# preamp.net
KiCad netlist of a schematic drawn in Altium Designer
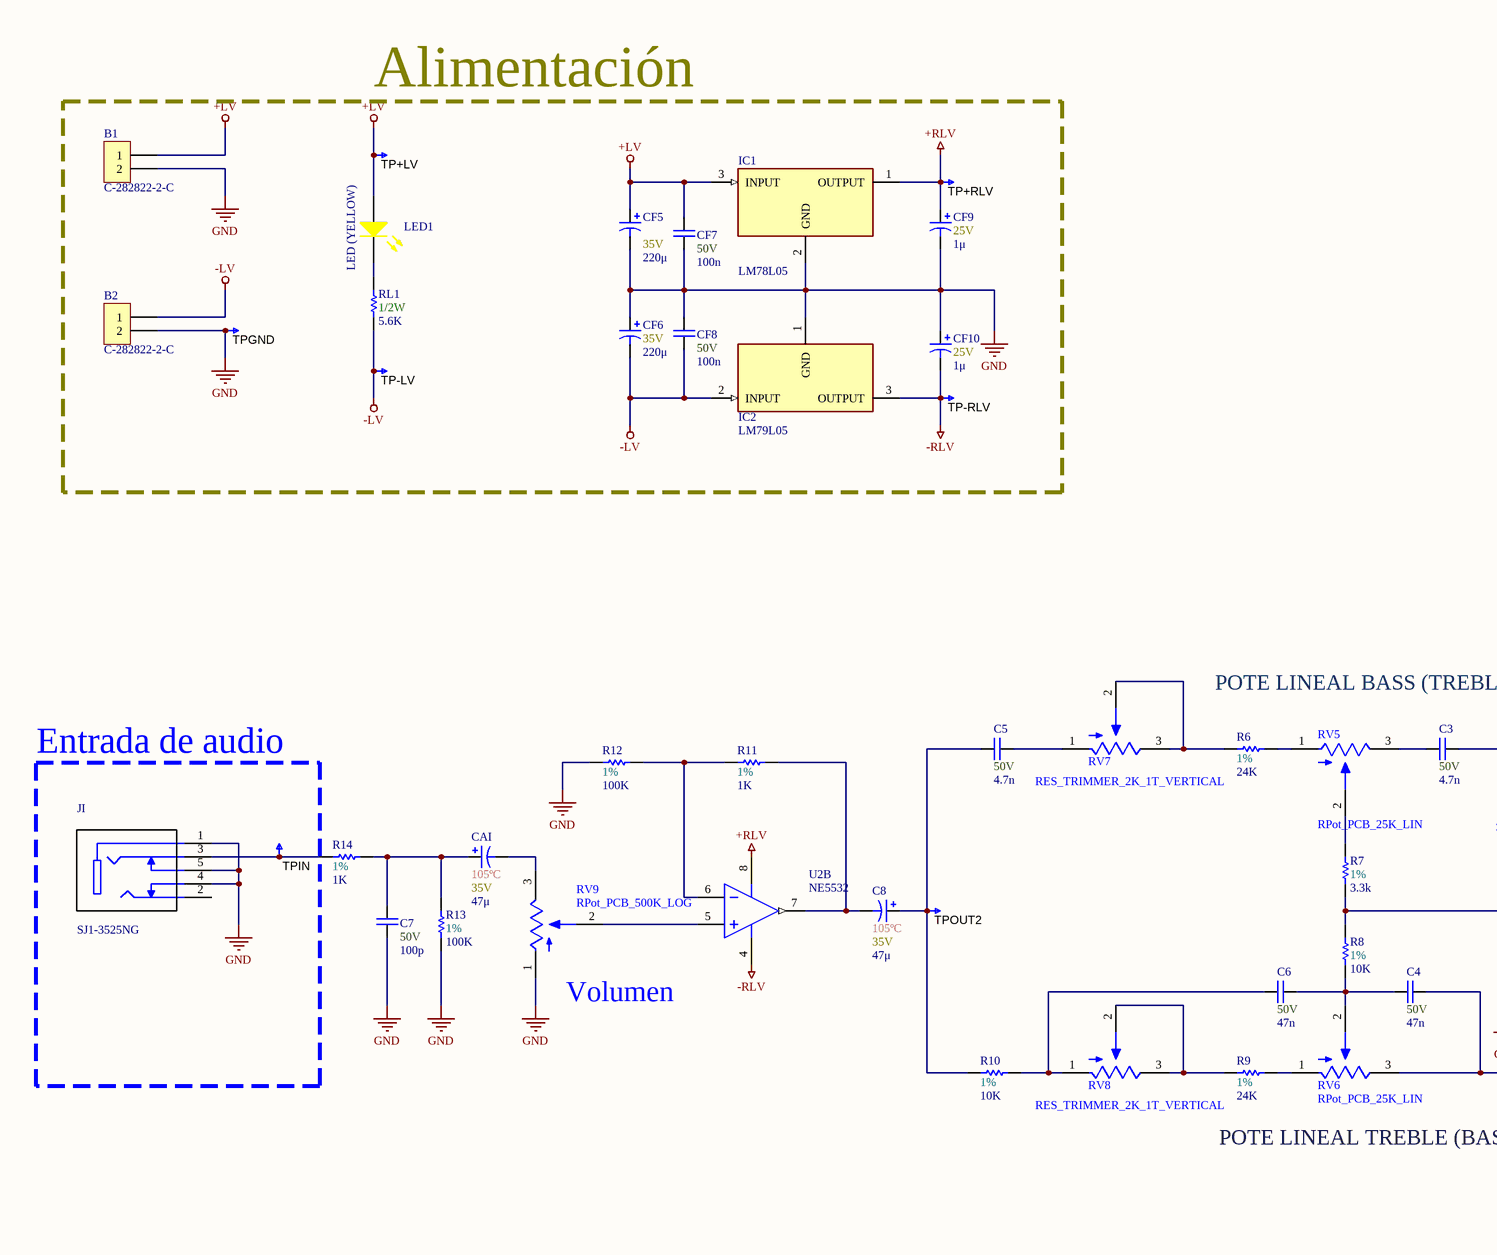
[diagram p0: preamp.SchDoc, left]
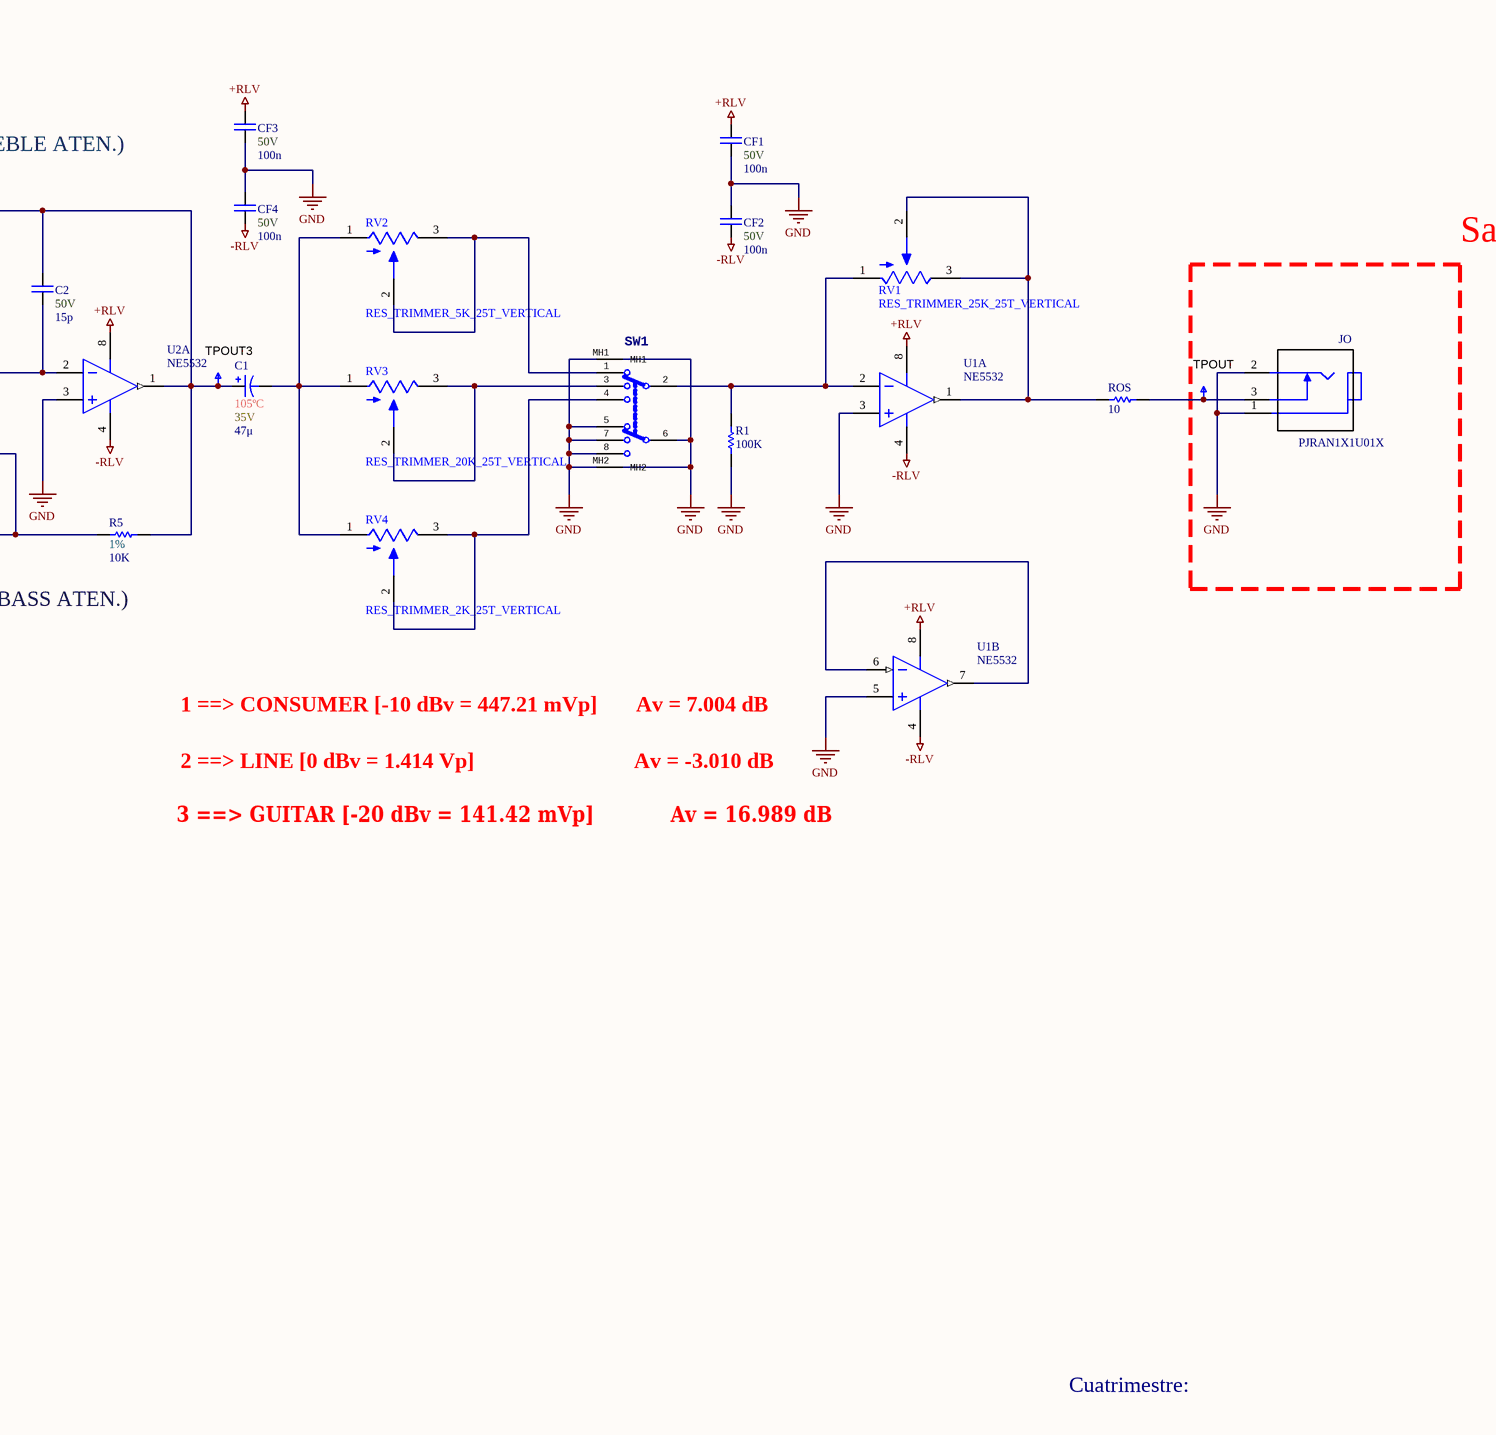
[diagram p1: preamp.SchDoc, right]

(export (version "E")
  (design (tool "Eeschema 10.0.6"))
  (components
    (comp (ref "B1")
      (value "C-282822-2-C")
      (footprint "TE-C-282822-2-C-PLUGGED")
      (description "TERMI-BLOK HEADER,ASSY90 2P - serie 282822 - 5.00mm")
      (fields (field (name "MANUFACTURER") "TE Connectivity"))
      (libsource (lib "Connectors") (part "C-282822-2-C"))
    )
    (comp (ref "B2")
      (value "C-282822-2-C")
      (footprint "TE-C-282822-2-C-PLUGGED")
      (description "TERMI-BLOK HEADER,ASSY90 2P - serie 282822 - 5.00mm")
      (fields (field (name "MANUFACTURER") "TE Connectivity"))
      (libsource (lib "Connectors") (part "C-282822-2-C"))
    )
    (comp (ref "C1")
      (value "47μ")
      (footprint "Al. Electrolytic 6.3mmx11.0mmx2.5mm-CLEAN")
      (description "Aluminum Electrolytic Capacitor 47μF 35V 20% 105º")
      (fields
        (field (name "TOLERANCE") "20%")
        (field (name "TEMPERATURE") "105ºC")
        (field (name "VOLTAGE") "35V")
        (field (name "Comment") "Al. Elect. 47u 35V 20% 105º")
      )
      (libsource (lib "Capacitors") (part "Al. Elect. 47u 35V 20% 105º"))
    )
    (comp (ref "C2")
      (value "15p")
      (footprint "Cer. pitch 5.08mm height 6.00mm")
      (description "Ceramic Capacitor 15pF 50V 10%")
      (fields
        (field (name "TOLERANCE") "10%")
        (field (name "VOLTAGE") "50V")
        (field (name "Comment") "Cer. 15p 50V 10%")
      )
      (libsource (lib "Capacitors") (part "Cer. 15p 50V 10%"))
    )
    (comp (ref "C3")
      (value "4.7n")
      (footprint "Cer. pitch 5.5mm height 6.0mm")
      (description "Ceramic Capacitor 4.7nF 50V 10%")
      (fields
        (field (name "TOLERANCE") "10%")
        (field (name "VOLTAGE") "50V")
        (field (name "Comment") "Cer. 4.7n 50V 10%")
      )
      (libsource (lib "Capacitors") (part "Cer. 4.7n 50V 10%"))
    )
    (comp (ref "C4")
      (value "47n")
      (footprint "Cer. pitch 5.5mm height 6.0mm")
      (description "Ceramic Capacitor 47nF 50V 10%")
      (fields
        (field (name "TOLERANCE") "10%")
        (field (name "VOLTAGE") "50V")
        (field (name "Comment") "Cer. 47n 50V 10%")
      )
      (libsource (lib "Capacitors") (part "Cer. 47n 50V 10%"))
    )
    (comp (ref "C5")
      (value "4.7n")
      (footprint "Cer. pitch 5.5mm height 6.0mm")
      (description "Ceramic Capacitor 4.7nF 50V 10%")
      (fields
        (field (name "TOLERANCE") "10%")
        (field (name "VOLTAGE") "50V")
        (field (name "Comment") "Cer. 4.7n 50V 10%")
      )
      (libsource (lib "Capacitors") (part "Cer. 4.7n 50V 10%"))
    )
    (comp (ref "C6")
      (value "47n")
      (footprint "Cer. pitch 5.5mm height 6.0mm")
      (description "Ceramic Capacitor 47nF 50V 10%")
      (fields
        (field (name "TOLERANCE") "10%")
        (field (name "VOLTAGE") "50V")
        (field (name "Comment") "Cer. 47n 50V 10%")
      )
      (libsource (lib "Capacitors") (part "Cer. 47n 50V 10%"))
    )
    (comp (ref "C7")
      (value "100p")
      (footprint "Cer. pitch 5.08mm height 6.00mm")
      (description "Ceramic Capacitor 100pF 50V 10%")
      (fields
        (field (name "TOLERANCE") "10%")
        (field (name "VOLTAGE") "50V")
        (field (name "Comment") "Cer. 100p 50V 10%")
      )
      (libsource (lib "Capacitors") (part "Cer. 100p 50V 10%"))
    )
    (comp (ref "C8")
      (value "47μ")
      (footprint "Al. Electrolytic 6.3mmx11.0mmx2.5mm-CLEAN")
      (description "Aluminum Electrolytic Capacitor 47μF 35V 20% 105º")
      (fields
        (field (name "TOLERANCE") "20%")
        (field (name "TEMPERATURE") "105ºC")
        (field (name "VOLTAGE") "35V")
        (field (name "Comment") "Al. Elect. 47u 35V 20% 105º")
      )
      (libsource (lib "") (part "Al. Elect. 47u 35V 20% 105º_1"))
    )
    (comp (ref "CAI")
      (value "47μ")
      (footprint "Al. Electrolytic 6.3mmx11.0mmx2.5mm-CLEAN")
      (description "Aluminum Electrolytic Capacitor 47μF 35V 20% 105º")
      (fields
        (field (name "TOLERANCE") "20%")
        (field (name "TEMPERATURE") "105ºC")
        (field (name "VOLTAGE") "35V")
        (field (name "Comment") "Al. Elect. 47u 35V 20% 105º")
      )
      (libsource (lib "Capacitors") (part "Al. Elect. 47u 35V 20% 105º"))
    )
    (comp (ref "CF1")
      (value "100n")
      (footprint "Cer. pitch 5.0mm height 5.5mm")
      (description "Ceramic Capacitor 100nF 50V 10%")
      (fields
        (field (name "TOLERANCE") "10%")
        (field (name "VOLTAGE") "50V")
        (field (name "Comment") "Cer. 100n 50V 10%")
      )
      (libsource (lib "Capacitors") (part "Cer. 100n 50V 10%"))
    )
    (comp (ref "CF2")
      (value "100n")
      (footprint "Cer. pitch 5.0mm height 5.5mm")
      (description "Ceramic Capacitor 100nF 50V 10%")
      (fields
        (field (name "TOLERANCE") "10%")
        (field (name "VOLTAGE") "50V")
        (field (name "Comment") "Cer. 100n 50V 10%")
      )
      (libsource (lib "Capacitors") (part "Cer. 100n 50V 10%"))
    )
    (comp (ref "CF3")
      (value "100n")
      (footprint "Cer. pitch 5.0mm height 5.5mm")
      (description "Ceramic Capacitor 100nF 50V 10%")
      (fields
        (field (name "TOLERANCE") "10%")
        (field (name "VOLTAGE") "50V")
        (field (name "Comment") "Cer. 100n 50V 10%")
      )
      (libsource (lib "Capacitors") (part "Cer. 100n 50V 10%"))
    )
    (comp (ref "CF4")
      (value "100n")
      (footprint "Cer. pitch 5.0mm height 5.5mm")
      (description "Ceramic Capacitor 100nF 50V 10%")
      (fields
        (field (name "TOLERANCE") "10%")
        (field (name "VOLTAGE") "50V")
        (field (name "Comment") "Cer. 100n 50V 10%")
      )
      (libsource (lib "Capacitors") (part "Cer. 100n 50V 10%"))
    )
    (comp (ref "CF5")
      (value "220μ")
      (footprint "Al. Electrolytic 8.0mmx13.0mmx3.5mm-CLEAN")
      (description "Aluminum Electrolytic Capacitor 220μF 35V 20% 105º")
      (fields
        (field (name "TOLERANCE") "20%")
        (field (name "VOLTAGE") "35V")
        (field (name "Comment") "Al. Elect. 220u 35V 20% 105º")
      )
      (libsource (lib "Capacitors") (part "Al. Elect. 220u 35V 20% 105º"))
    )
    (comp (ref "CF6")
      (value "220μ")
      (footprint "Al. Electrolytic 8.0mmx13.0mmx3.5mm-CLEAN")
      (description "Aluminum Electrolytic Capacitor 220μF 35V 20% 105º")
      (fields
        (field (name "TOLERANCE") "20%")
        (field (name "VOLTAGE") "35V")
        (field (name "Comment") "Al. Elect. 220u 35V 20% 105º")
      )
      (libsource (lib "Capacitors") (part "Al. Elect. 220u 35V 20% 105º"))
    )
    (comp (ref "CF7")
      (value "100n")
      (footprint "Cer. pitch 5.0mm height 5.5mm")
      (description "Ceramic Capacitor 100nF 50V 10%")
      (fields
        (field (name "TOLERANCE") "10%")
        (field (name "VOLTAGE") "50V")
        (field (name "Comment") "Cer. 100n 50V 10%")
      )
      (libsource (lib "Capacitors") (part "Cer. 100n 50V 10%"))
    )
    (comp (ref "CF8")
      (value "100n")
      (footprint "Cer. pitch 5.0mm height 5.5mm")
      (description "Ceramic Capacitor 100nF 50V 10%")
      (fields
        (field (name "TOLERANCE") "10%")
        (field (name "VOLTAGE") "50V")
        (field (name "Comment") "Cer. 100n 50V 10%")
      )
      (libsource (lib "Capacitors") (part "Cer. 100n 50V 10%"))
    )
    (comp (ref "CF9")
      (value "1μ")
      (footprint "Tantalum Electrolytic 4.5mmx8.0mmx0.254mm-CLEAN")
      (description "Tantalum Electrolytic Capacitor 1μF 25V 10%")
      (fields
        (field (name "TOLERANCE") "10%")
        (field (name "VOLTAGE") "25V")
        (field (name "Comment") "Tant. Elect. 1u 25V 10%")
      )
      (libsource (lib "Capacitors") (part "Tant. Elect. 1u 25V 10%"))
    )
    (comp (ref "CF10")
      (value "1μ")
      (footprint "Tantalum Electrolytic 4.5mmx8.0mmx0.254mm-CLEAN")
      (description "Tantalum Electrolytic Capacitor 1μF 25V 10%")
      (fields
        (field (name "TOLERANCE") "10%")
        (field (name "VOLTAGE") "25V")
        (field (name "Comment") "Tant. Elect. 1u 25V 10%")
      )
      (libsource (lib "Capacitors") (part "Tant. Elect. 1u 25V 10%"))
    )
    (comp (ref "IC1")
      (value "LM78L05")
      (footprint "TO-92-1")
      (description "5V fixed regulator - 100mA")
      (fields (field (name "MANUFACTURER_PART_NUMBER") "LM7805"))
      (libsource (lib "FIXED_REGULATORS") (part "LM78L05"))
    )
    (comp (ref "IC2")
      (value "LM79L05")
      (footprint "TO-92-1")
      (description "-5V fixed regulator - 100mA")
      (fields (field (name "MANUFACTURER_PART_NUMBER") "LM7805"))
      (libsource (lib "FIXED_REGULATORS") (part "LM79L05"))
    )
    (comp (ref "JI")
      (value "SJ1-3525NG")
      (footprint "*CUI_SJ1-3525NG")
      (libsource (lib "Connectors") (part "SJ1-3525NG"))
    )
    (comp (ref "JO")
      (value "PJRAN1X1U01X")
      (footprint "*SWITCHCRAFT_PJRAN1X1U01X")
      (description "Conn Phono Jack F 3 POS Solder RA Thru-Hole 3 Terminal 1 Port")
      (fields (field (name "MF") "Switchcraft"))
      (libsource (lib "Connectors") (part "PJRAN1X1U01X"))
    )
    (comp (ref "LED1")
      (value "LED (YELLOW)")
      (footprint "LED_5MM_YELLOW")
      (description "Typical LED (YELLOW)")
      (fields (field (name "PUBLISHER") "Altium Limited"))
      (libsource (lib "GENERIC_LED") (part "LED (YELLOW)"))
    )
    (comp (ref "R1")
      (value "100K")
      (footprint "AXIAL-0.4-E24-0_25W-100k")
      (description "Resistor 100KΩ 1/4W 5%")
      (fields (field (name "POWER") "1/4W") (field (name "TOLERANCE") "5%"))
      (libsource (lib "Resistors") (part "Resistor 100K 1/4W 5%"))
    )
    (comp (ref "R5")
      (value "10K")
      (footprint "AXIAL-0.4-E24-0_25W-10k-1%")
      (description "Resistor 10KΩ 1/4W 1%")
      (fields
        (field (name "POWER") "1/4W")
        (field (name "TOLERANCE") "1%")
        (field (name "Comment") "Resistor 10K 1/4W 1%")
      )
      (libsource (lib "Resistors") (part "Resistor 10K 1/4W 1%"))
    )
    (comp (ref "R6")
      (value "24K")
      (footprint "AXIAL-0.4-E24-0_25W-24k-1%")
      (description "Resistor 24KΩ 1/4W 1%")
      (fields
        (field (name "POWER") "1/4W")
        (field (name "TOLERANCE") "1%")
        (field (name "Comment") "Resistor 24K 1/4W 1%")
      )
      (libsource (lib "Resistors") (part "Resistor 24K 1/4W 1%"))
    )
    (comp (ref "R7")
      (value "3.3k")
      (footprint "AXIAL-0.4-E24-0_25W-3.3k-1%")
      (description "Resistor 3.3kΩ 1/4W 1%")
      (fields
        (field (name "POWER") "1/4W")
        (field (name "TOLERANCE") "1%")
        (field (name "Comment") "Resistor 3.3k 1/4W 1%")
      )
      (libsource (lib "Resistors") (part "Resistor 3.3k 1/4W 1%"))
    )
    (comp (ref "R8")
      (value "10K")
      (footprint "AXIAL-0.4-E24-0_25W-10k-1%")
      (description "Resistor 10KΩ 1/4W 1%")
      (fields
        (field (name "POWER") "1/4W")
        (field (name "TOLERANCE") "1%")
        (field (name "Comment") "Resistor 10K 1/4W 1%")
      )
      (libsource (lib "Resistors") (part "Resistor 10K 1/4W 1%"))
    )
    (comp (ref "R9")
      (value "24K")
      (footprint "AXIAL-0.4-E24-0_25W-24k-1%")
      (description "Resistor 24KΩ 1/4W 1%")
      (fields
        (field (name "POWER") "1/4W")
        (field (name "TOLERANCE") "1%")
        (field (name "Comment") "Resistor 24K 1/4W 1%")
      )
      (libsource (lib "Resistors") (part "Resistor 24K 1/4W 1%"))
    )
    (comp (ref "R10")
      (value "10K")
      (footprint "AXIAL-0.4-E24-0_25W-10k-1%")
      (description "Resistor 10KΩ 1/4W 1%")
      (fields
        (field (name "POWER") "1/4W")
        (field (name "TOLERANCE") "1%")
        (field (name "Comment") "Resistor 10K 1/4W 1%")
      )
      (libsource (lib "Resistors") (part "Resistor 10K 1/4W 1%"))
    )
    (comp (ref "R11")
      (value "1K")
      (footprint "AXIAL-0.4-E24-0_25W-1k-1%")
      (description "Resistor 1KΩ 1/4W 1%")
      (fields
        (field (name "POWER") "1/4W")
        (field (name "TOLERANCE") "1%")
        (field (name "Comment") "Resistor 1K 1/4W 1%")
      )
      (libsource (lib "Resistors") (part "Resistor 1K 1/4W 1%"))
    )
    (comp (ref "R12")
      (value "100K")
      (footprint "AXIAL-0.4-E24-0_25W-100k-1%")
      (description "Resistor 100KΩ 1/4W 1%")
      (fields
        (field (name "POWER") "1/4W")
        (field (name "TOLERANCE") "1%")
        (field (name "Comment") "Resistor 100K 1/4W 1%")
      )
      (libsource (lib "Resistors") (part "Resistor 100K 1/4W 1%"))
    )
    (comp (ref "R13")
      (value "100K")
      (footprint "AXIAL-0.4-E24-0_25W-100k-1%")
      (description "Resistor 100KΩ 1/4W 1%")
      (fields
        (field (name "POWER") "1/4W")
        (field (name "TOLERANCE") "1%")
        (field (name "Comment") "Resistor 100K 1/4W 1%")
      )
      (libsource (lib "Resistors") (part "Resistor 100K 1/4W 1%"))
    )
    (comp (ref "R14")
      (value "1K")
      (footprint "AXIAL-0.4-E24-0_25W-1k-1%")
      (description "Resistor 1KΩ 1/4W 1%")
      (fields
        (field (name "POWER") "1/4W")
        (field (name "TOLERANCE") "1%")
        (field (name "Comment") "Resistor 1K 1/4W 1%")
      )
      (libsource (lib "Resistors") (part "Resistor 1K 1/4W 1%"))
    )
    (comp (ref "RL1")
      (value "5.6K")
      (footprint "AXIAL-0.5-E24-0_5W-5.6K")
      (description "Resistor 5.6KΩ 1/2W 5%")
      (fields
        (field (name "TOLERANCE") "5%")
        (field (name "POWER") "1/2W")
        (field (name "Comment") "Resistor 5.6K 1/2W 5%")
      )
      (libsource (lib "Resistors") (part "Resistor 5.6K 1/2W 5%"))
    )
    (comp (ref "ROS")
      (value "10")
      (footprint "AXIAL-0.4-E24-0_25W-10")
      (description "Resistor 10Ω 1/4W 5%")
      (fields (field (name "POWER") "1/4W") (field (name "TOLERANCE") "5%"))
      (libsource (lib "Resistors") (part "Resistor 10 1/4W 5%"))
    )
    (comp (ref "RV1")
      (value "RES_TRIMMER_25K_25T_VERTICAL")
      (footprint "POT_3296W")
      (description "Trimmer Vertical 25K 500mW 25-turn")
      (fields (field (name "TOLERANCE") "±10%") (field (name "POWER") "25k"))
      (libsource (lib "Resistors") (part "RES_TRIMMER_25K_25T_VERTICAL"))
    )
    (comp (ref "RV2")
      (value "RES_TRIMMER_5K_25T_VERTICAL")
      (footprint "POT_3296W")
      (description "Trimmer Vertical 5K 500mW 25-turn")
      (fields (field (name "TOLERANCE") "±10%"))
      (libsource (lib "Resistors") (part "RES_TRIMMER_5K_25T_VERTICAL"))
    )
    (comp (ref "RV3")
      (value "RES_TRIMMER_20K_25T_VERTICAL")
      (footprint "POT_3296W")
      (description "Trimmer Vertical 20K 500mW 25-turn")
      (fields (field (name "TOLERANCE") "±10%"))
      (libsource (lib "Resistors") (part "RES_TRIMMER_20K_25T_VERTICAL"))
    )
    (comp (ref "RV4")
      (value "RES_TRIMMER_2K_25T_VERTICAL")
      (footprint "POT_3296W")
      (description "Trimmer Vertical 2K 500mW 25-turn")
      (fields (field (name "TOLERANCE") "±10%"))
      (libsource (lib "Resistors") (part "RES_TRIMMER_2K_25T_VERTICAL"))
    )
    (comp (ref "RV5")
      (value "RPot_PCB_25K_LIN")
      (footprint "POTE16mm")
      (description "25K PCB LIN Potentiometer")
      (libsource (lib "Resistors") (part "RPot_PCB_25K_LIN"))
    )
    (comp (ref "RV6")
      (value "RPot_PCB_25K_LIN")
      (footprint "POTE16mm")
      (description "25K PCB LIN Potentiometer")
      (libsource (lib "Resistors") (part "RPot_PCB_25K_LIN"))
    )
    (comp (ref "RV7")
      (value "RES_TRIMMER_2K_1T_VERTICAL")
      (footprint "POT_3386W")
      (description "Trimmer Vertical 2K 500mW 1-turn")
      (fields (field (name "TOLERANCE") "±10%"))
      (libsource (lib "Resistors") (part "RES_TRIMMER_2K_1T_VERTICAL"))
    )
    (comp (ref "RV8")
      (value "RES_TRIMMER_2K_1T_VERTICAL")
      (footprint "POT_3386W")
      (description "Trimmer Vertical 2K 500mW 1-turn")
      (fields (field (name "TOLERANCE") "±10%"))
      (libsource (lib "Resistors") (part "RES_TRIMMER_2K_1T_VERTICAL"))
    )
    (comp (ref "RV9")
      (value "RPot_PCB_500K_LOG")
      (footprint "POTE16mm")
      (description "500K PCB LOG Potentiometer")
      (libsource (lib "Resistors") (part "RPot_PCB_500K_LOG"))
    )
    (comp (ref "SW1")
      (value "SWITCH SLIDE DP3T 200MA 30V")
      (footprint "E-SWITCH_EG2315")
      (description "EG Series DP3T On-On-On 0.2 A Right Angle Through Hole Slide Switch")
      (fields
        (field (name "MOUSER_PART_NUMBER") "612-EG2315")
        (field (name "MPN") "EG2315")
        (field (name "LIBRARYNAME") "Upverter Library")
      )
      (libsource (lib "Switches") (part "E-SWITCH_EG2315E"))
    )
    (comp (ref "TP+LV")
      (value "TESTPOINT_THT")
      (footprint "TP-THT-MULTI")
      (description "Test Point PCB mount Multi-purpose Black")
      (fields (field (name "PBL PART NUMBER") "3100-xxx"))
      (libsource (lib "Test Points and Jumpers") (part "TESTPOINT_THT"))
    )
    (comp (ref "TP+RLV")
      (value "TESTPOINT_THT")
      (footprint "TP-THT-MULTI")
      (description "Test Point PCB mount Multi-purpose Black")
      (fields (field (name "PBL PART NUMBER") "3100-xxx"))
      (libsource (lib "Test Points and Jumpers") (part "TESTPOINT_THT"))
    )
    (comp (ref "TP-LV")
      (value "TESTPOINT_THT")
      (footprint "TP-THT-MULTI")
      (description "Test Point PCB mount Multi-purpose Black")
      (fields (field (name "PBL PART NUMBER") "3100-xxx"))
      (libsource (lib "Test Points and Jumpers") (part "TESTPOINT_THT"))
    )
    (comp (ref "TP-RLV")
      (value "TESTPOINT_THT")
      (footprint "TP-THT-MULTI")
      (description "Test Point PCB mount Multi-purpose Black")
      (fields (field (name "PBL PART NUMBER") "3100-xxx"))
      (libsource (lib "Test Points and Jumpers") (part "TESTPOINT_THT"))
    )
    (comp (ref "TPGND")
      (value "TESTPOINT_THT")
      (footprint "TP-THT-MULTI")
      (description "Test Point PCB mount Multi-purpose Black")
      (fields (field (name "PBL PART NUMBER") "3100-xxx"))
      (libsource (lib "Test Points and Jumpers") (part "TESTPOINT_THT"))
    )
    (comp (ref "TPIN")
      (value "TESTPOINT_THT")
      (footprint "TP-THT-MULTI")
      (description "Test Point PCB mount Multi-purpose Black")
      (fields (field (name "PBL PART NUMBER") "3100-xxx"))
      (libsource (lib "Test Points and Jumpers") (part "TESTPOINT_THT"))
    )
    (comp (ref "TPOUT")
      (value "TESTPOINT_THT")
      (footprint "TP-THT-MULTI")
      (description "Test Point PCB mount Multi-purpose Black")
      (fields (field (name "PBL PART NUMBER") "3100-xxx"))
      (libsource (lib "Test Points and Jumpers") (part "TESTPOINT_THT"))
    )
    (comp (ref "TPOUT2")
      (value "TESTPOINT_THT")
      (footprint "TP-THT-MULTI")
      (description "Test Point PCB mount Multi-purpose Black")
      (fields (field (name "PBL PART NUMBER") "3100-xxx"))
      (libsource (lib "Test Points and Jumpers") (part "TESTPOINT_THT"))
    )
    (comp (ref "TPOUT3")
      (value "TESTPOINT_THT")
      (footprint "TP-THT-MULTI")
      (description "Test Point PCB mount Multi-purpose Black")
      (fields (field (name "PBL PART NUMBER") "3100-xxx"))
      (libsource (lib "Test Points and Jumpers") (part "TESTPOINT_THT"))
    )
    (comp (ref "U1")
      (value "NE5532")
      (footprint "DIP8 - W SOCKET")
      (description "Dual Low-Noise Operational Amplifiers")
      (fields (field (name "MANUFACTURER") "Texas Instruments"))
      (libsource (lib "National Semiconductor Amplifier") (part "NE5532"))
    )
    (comp (ref "U2")
      (value "NE5532")
      (footprint "DIP8 - W SOCKET")
      (description "Dual Low-Noise Operational Amplifiers")
      (fields (field (name "MANUFACTURER") "Texas Instruments"))
      (libsource (lib "National Semiconductor Amplifier") (part "NE5532"))
    )
  )
  (nets
    (net (code "1") (name "+LV") (class "Default")
      (node (ref "B1") (pin "1") (pinfunction "1_1") (pintype "power_in"))
      (node (ref "CF5") (pin "1") (pinfunction "1_1") (pintype "passive"))
      (node (ref "CF7") (pin "2") (pinfunction "2_2") (pintype "passive"))
      (node (ref "IC1") (pin "3") (pinfunction "INPUT_3") (pintype "input"))
      (node (ref "LED1") (pin "A") (pinfunction "A_A") (pintype "passive"))
      (node (ref "TP+LV") (pin "1") (pintype "passive"))
    )
    (net (code "2") (name "+RLV") (class "Default")
      (node (ref "CF1") (pin "2") (pinfunction "2_2") (pintype "passive"))
      (node (ref "CF3") (pin "2") (pinfunction "2_2") (pintype "passive"))
      (node (ref "CF9") (pin "1") (pinfunction "1_1") (pintype "passive"))
      (node (ref "IC1") (pin "1") (pinfunction "OUTPUT_1") (pintype "power_in"))
      (node (ref "TP+RLV") (pin "1") (pintype "passive"))
      (node (ref "U1") (pin "8") (pinfunction "V+_8") (pintype "power_in"))
      (node (ref "U2") (pin "8") (pinfunction "V+_8") (pintype "power_in"))
    )
    (net (code "3") (name "-LV") (class "Default")
      (node (ref "B2") (pin "1") (pinfunction "1_1") (pintype "power_in"))
      (node (ref "CF6") (pin "2") (pinfunction "2_2") (pintype "passive"))
      (node (ref "CF8") (pin "1") (pinfunction "1_1") (pintype "passive"))
      (node (ref "IC2") (pin "2") (pinfunction "INPUT_2") (pintype "input"))
      (node (ref "RL1") (pin "1") (pinfunction "1_1") (pintype "passive"))
      (node (ref "TP-LV") (pin "1") (pintype "passive"))
    )
    (net (code "4") (name "-RLV") (class "Default")
      (node (ref "CF10") (pin "2") (pinfunction "2_2") (pintype "passive"))
      (node (ref "CF2") (pin "1") (pinfunction "1_1") (pintype "passive"))
      (node (ref "CF4") (pin "1") (pinfunction "1_1") (pintype "passive"))
      (node (ref "IC2") (pin "3") (pinfunction "OUTPUT_3") (pintype "power_in"))
      (node (ref "TP-RLV") (pin "1") (pintype "passive"))
      (node (ref "U1") (pin "4") (pinfunction "V-_4") (pintype "power_in"))
      (node (ref "U2") (pin "4") (pinfunction "V-_4") (pintype "power_in"))
    )
    (net (code "5") (name "GND") (class "Default")
      (node (ref "B1") (pin "2") (pinfunction "2_2") (pintype "passive"))
      (node (ref "B2") (pin "2") (pinfunction "2_2") (pintype "passive"))
      (node (ref "C7") (pin "2") (pinfunction "2_2") (pintype "passive"))
      (node (ref "CF1") (pin "1") (pinfunction "1_1") (pintype "passive"))
      (node (ref "CF10") (pin "1") (pinfunction "1_1") (pintype "passive"))
      (node (ref "CF2") (pin "2") (pinfunction "2_2") (pintype "passive"))
      (node (ref "CF3") (pin "1") (pinfunction "1_1") (pintype "passive"))
      (node (ref "CF4") (pin "2") (pinfunction "2_2") (pintype "passive"))
      (node (ref "CF5") (pin "2") (pinfunction "2_2") (pintype "passive"))
      (node (ref "CF6") (pin "1") (pinfunction "1_1") (pintype "passive"))
      (node (ref "CF7") (pin "1") (pinfunction "1_1") (pintype "passive"))
      (node (ref "CF8") (pin "2") (pinfunction "2_2") (pintype "passive"))
      (node (ref "CF9") (pin "2") (pinfunction "2_2") (pintype "passive"))
      (node (ref "IC1") (pin "2") (pinfunction "GND_2") (pintype "passive"))
      (node (ref "IC2") (pin "1") (pinfunction "GND_1") (pintype "passive"))
      (node (ref "JI") (pin "1") (pinfunction "1_1") (pintype "passive"))
      (node (ref "JI") (pin "4") (pinfunction "4_4") (pintype "passive"))
      (node (ref "JI") (pin "5") (pinfunction "5_5") (pintype "passive"))
      (node (ref "JO") (pin "1") (pinfunction "1_1") (pintype "passive"))
      (node (ref "JO") (pin "2") (pinfunction "2_2") (pintype "passive"))
      (node (ref "R1") (pin "1") (pinfunction "1_1") (pintype "passive"))
      (node (ref "R12") (pin "1") (pinfunction "1_1") (pintype "passive"))
      (node (ref "R13") (pin "1") (pinfunction "1_1") (pintype "passive"))
      (node (ref "RV9") (pin "1") (pinfunction "A_1") (pintype "passive"))
      (node (ref "SW1") (pin "5") (pinfunction "5_5") (pintype "passive"))
      (node (ref "SW1") (pin "6") (pinfunction "2_COM_6") (pintype "passive"))
      (node (ref "SW1") (pin "7") (pinfunction "7_7") (pintype "passive"))
      (node (ref "SW1") (pin "8") (pinfunction "8_8") (pintype "passive"))
      (node (ref "SW1") (pin "MH1") (pinfunction "MH1_MH1") (pintype "passive"))
      (node (ref "SW1") (pin "MH2") (pinfunction "MH2_MH2") (pintype "passive"))
      (node (ref "TPGND") (pin "1") (pintype "passive"))
      (node (ref "U1") (pin "3") (pinfunction "INA+_3") (pintype "input"))
      (node (ref "U1") (pin "5") (pinfunction "INB+_5") (pintype "passive"))
      (node (ref "U2") (pin "3") (pinfunction "INA+_3") (pintype "input"))
    )
    (net (code "6") (name "Net-(C5-Pad1)") (class "Default")
      (node (ref "C5") (pin "1") (pinfunction "1_1") (pintype "passive"))
      (node (ref "C8") (pin "1") (pinfunction "1_1") (pintype "passive"))
      (node (ref "R10") (pin "1") (pinfunction "1_1") (pintype "passive"))
      (node (ref "TPOUT2") (pin "1") (pintype "passive"))
    )
    (net (code "7") (name "Net-(C7-Pad1)") (class "Default")
      (node (ref "C7") (pin "1") (pinfunction "1_1") (pintype "passive"))
      (node (ref "CAI") (pin "1") (pinfunction "1_1") (pintype "passive"))
      (node (ref "R13") (pin "2") (pinfunction "2_2") (pintype "passive"))
      (node (ref "R14") (pin "2") (pinfunction "2_2") (pintype "passive"))
    )
    (net (code "8") (name "Net-(JI-Pad3)") (class "Default")
      (node (ref "JI") (pin "3") (pinfunction "3_3") (pintype "passive"))
      (node (ref "R14") (pin "1") (pinfunction "1_1") (pintype "passive"))
      (node (ref "TPIN") (pin "1") (pintype "passive"))
    )
    (net (code "9") (name "Net-(JO-Pad3)") (class "Default")
      (node (ref "JO") (pin "3") (pinfunction "3_3") (pintype "passive"))
      (node (ref "ROS") (pin "2") (pinfunction "2_2") (pintype "passive"))
      (node (ref "TPOUT") (pin "1") (pintype "passive"))
    )
    (net (code "10") (name "Net-(LED1-PadK)") (class "Default")
      (node (ref "LED1") (pin "K") (pinfunction "K_K") (pintype "passive"))
      (node (ref "RL1") (pin "2") (pinfunction "2_2") (pintype "passive"))
    )
    (net (code "11") (name "Net-(RV1-A)") (class "Default")
      (node (ref "R1") (pin "2") (pinfunction "2_2") (pintype "passive"))
      (node (ref "RV1") (pin "1") (pinfunction "A_1") (pintype "passive"))
      (node (ref "SW1") (pin "2") (pinfunction "1_COM_2") (pintype "passive"))
      (node (ref "U1") (pin "2") (pinfunction "INA-_2") (pintype "input"))
    )
    (net (code "12") (name "Net-(RV1-B)") (class "Default")
      (node (ref "ROS") (pin "1") (pinfunction "1_1") (pintype "passive"))
      (node (ref "RV1") (pin "2") (pinfunction "B_2") (pintype "passive"))
      (node (ref "RV1") (pin "3") (pinfunction "C_3") (pintype "passive"))
      (node (ref "U1") (pin "1") (pinfunction "OUTA_1") (pintype "output"))
    )
    (net (code "13") (name "Net-(RV2-A)") (class "Default")
      (node (ref "C1") (pin "2") (pinfunction "2_2") (pintype "passive"))
      (node (ref "RV2") (pin "1") (pinfunction "A_1") (pintype "passive"))
      (node (ref "RV3") (pin "1") (pinfunction "A_1") (pintype "passive"))
      (node (ref "RV4") (pin "1") (pinfunction "A_1") (pintype "passive"))
    )
    (net (code "14") (name "Net-(RV2-B)") (class "Default")
      (node (ref "RV2") (pin "2") (pinfunction "B_2") (pintype "passive"))
      (node (ref "RV2") (pin "3") (pinfunction "C_3") (pintype "passive"))
      (node (ref "SW1") (pin "1") (pinfunction "1_1") (pintype "passive"))
    )
    (net (code "15") (name "Net-(RV3-B)") (class "Default")
      (node (ref "RV3") (pin "2") (pinfunction "B_2") (pintype "passive"))
      (node (ref "RV3") (pin "3") (pinfunction "C_3") (pintype "passive"))
      (node (ref "SW1") (pin "3") (pinfunction "3_3") (pintype "passive"))
    )
    (net (code "16") (name "Net-(RV4-B)") (class "Default")
      (node (ref "RV4") (pin "2") (pinfunction "B_2") (pintype "passive"))
      (node (ref "RV4") (pin "3") (pinfunction "C_3") (pintype "passive"))
      (node (ref "SW1") (pin "4") (pinfunction "4_4") (pintype "passive"))
    )
    (net (code "17") (name "Net-(RV5-A)") (class "Default")
      (node (ref "R6") (pin "1") (pinfunction "1_1") (pintype "passive"))
      (node (ref "RV5") (pin "1") (pinfunction "A_1") (pintype "passive"))
    )
    (net (code "18") (name "Net-(RV5-B)") (class "Default")
      (node (ref "R7") (pin "1") (pinfunction "1_1") (pintype "passive"))
      (node (ref "RV5") (pin "2") (pinfunction "B_2") (pintype "passive"))
    )
    (net (code "19") (name "Net-(RV5-C)") (class "Default")
      (node (ref "C3") (pin "1") (pinfunction "1_1") (pintype "passive"))
      (node (ref "RV5") (pin "3") (pinfunction "C_3") (pintype "passive"))
    )
    (net (code "20") (name "Net-(RV6-A)") (class "Default")
      (node (ref "R9") (pin "1") (pinfunction "1_1") (pintype "passive"))
      (node (ref "RV6") (pin "1") (pinfunction "A_1") (pintype "passive"))
    )
    (net (code "21") (name "Net-(RV6-B)") (class "Default")
      (node (ref "C4") (pin "1") (pinfunction "1_1") (pintype "passive"))
      (node (ref "C6") (pin "2") (pinfunction "2_2") (pintype "passive"))
      (node (ref "R8") (pin "1") (pinfunction "1_1") (pintype "passive"))
      (node (ref "RV6") (pin "2") (pinfunction "B_2") (pintype "passive"))
    )
    (net (code "22") (name "Net-(RV6-C)") (class "Default")
      (node (ref "C4") (pin "2") (pinfunction "2_2") (pintype "passive"))
      (node (ref "R5") (pin "1") (pinfunction "1_1") (pintype "passive"))
      (node (ref "RV6") (pin "3") (pinfunction "C_3") (pintype "passive"))
    )
    (net (code "23") (name "Net-(RV7-A)") (class "Default")
      (node (ref "C5") (pin "2") (pinfunction "2_2") (pintype "passive"))
      (node (ref "RV7") (pin "1") (pinfunction "A_1") (pintype "passive"))
    )
    (net (code "24") (name "Net-(RV7-B)") (class "Default")
      (node (ref "R6") (pin "2") (pinfunction "2_2") (pintype "passive"))
      (node (ref "RV7") (pin "2") (pinfunction "B_2") (pintype "passive"))
      (node (ref "RV7") (pin "3") (pinfunction "C_3") (pintype "passive"))
    )
    (net (code "25") (name "Net-(RV8-A)") (class "Default")
      (node (ref "C6") (pin "1") (pinfunction "1_1") (pintype "passive"))
      (node (ref "R10") (pin "2") (pinfunction "2_2") (pintype "passive"))
      (node (ref "RV8") (pin "1") (pinfunction "A_1") (pintype "passive"))
    )
    (net (code "26") (name "Net-(RV8-B)") (class "Default")
      (node (ref "R9") (pin "2") (pinfunction "2_2") (pintype "passive"))
      (node (ref "RV8") (pin "2") (pinfunction "B_2") (pintype "passive"))
      (node (ref "RV8") (pin "3") (pinfunction "C_3") (pintype "passive"))
    )
    (net (code "27") (name "Net-(RV9-B)") (class "Default")
      (node (ref "RV9") (pin "2") (pinfunction "B_2") (pintype "passive"))
      (node (ref "U2") (pin "5") (pinfunction "INB+_5") (pintype "passive"))
    )
    (net (code "28") (name "Net-(RV9-C)") (class "Default")
      (node (ref "CAI") (pin "2") (pinfunction "2_2") (pintype "passive"))
      (node (ref "RV9") (pin "3") (pinfunction "C_3") (pintype "passive"))
    )
    (net (code "29") (name "Net-(U1B-INB-)") (class "Default")
      (node (ref "U1") (pin "6") (pinfunction "INB-_6") (pintype "passive"))
      (node (ref "U1") (pin "7") (pinfunction "OUTB_7") (pintype "output"))
    )
    (net (code "30") (name "Net-(U2A-INA-)") (class "Default")
      (node (ref "C2") (pin "1") (pinfunction "1_1") (pintype "passive"))
      (node (ref "R7") (pin "2") (pinfunction "2_2") (pintype "passive"))
      (node (ref "R8") (pin "2") (pinfunction "2_2") (pintype "passive"))
      (node (ref "U2") (pin "2") (pinfunction "INA-_2") (pintype "input"))
    )
    (net (code "31") (name "Net-(U2A-OUTA)") (class "Default")
      (node (ref "C1") (pin "1") (pinfunction "1_1") (pintype "passive"))
      (node (ref "C2") (pin "2") (pinfunction "2_2") (pintype "passive"))
      (node (ref "C3") (pin "2") (pinfunction "2_2") (pintype "passive"))
      (node (ref "R5") (pin "2") (pinfunction "2_2") (pintype "passive"))
      (node (ref "TPOUT3") (pin "1") (pintype "passive"))
      (node (ref "U2") (pin "1") (pinfunction "OUTA_1") (pintype "output"))
    )
    (net (code "32") (name "Net-(U2B-INB-)") (class "Default")
      (node (ref "R11") (pin "2") (pinfunction "2_2") (pintype "passive"))
      (node (ref "R12") (pin "2") (pinfunction "2_2") (pintype "passive"))
      (node (ref "U2") (pin "6") (pinfunction "INB-_6") (pintype "passive"))
    )
    (net (code "33") (name "Net-(U2B-OUTB)") (class "Default")
      (node (ref "C8") (pin "2") (pinfunction "2_2") (pintype "passive"))
      (node (ref "R11") (pin "1") (pinfunction "1_1") (pintype "passive"))
      (node (ref "U2") (pin "7") (pinfunction "OUTB_7") (pintype "output"))
    )
    (net (code "34") (name "unconnected-(JI-Pad2)") (class "Default")
      (node (ref "JI") (pin "2") (pinfunction "2_2") (pintype "passive"))
    )
  )
)
